# touch.net
KiCad netlist of a schematic drawn in EAGLE
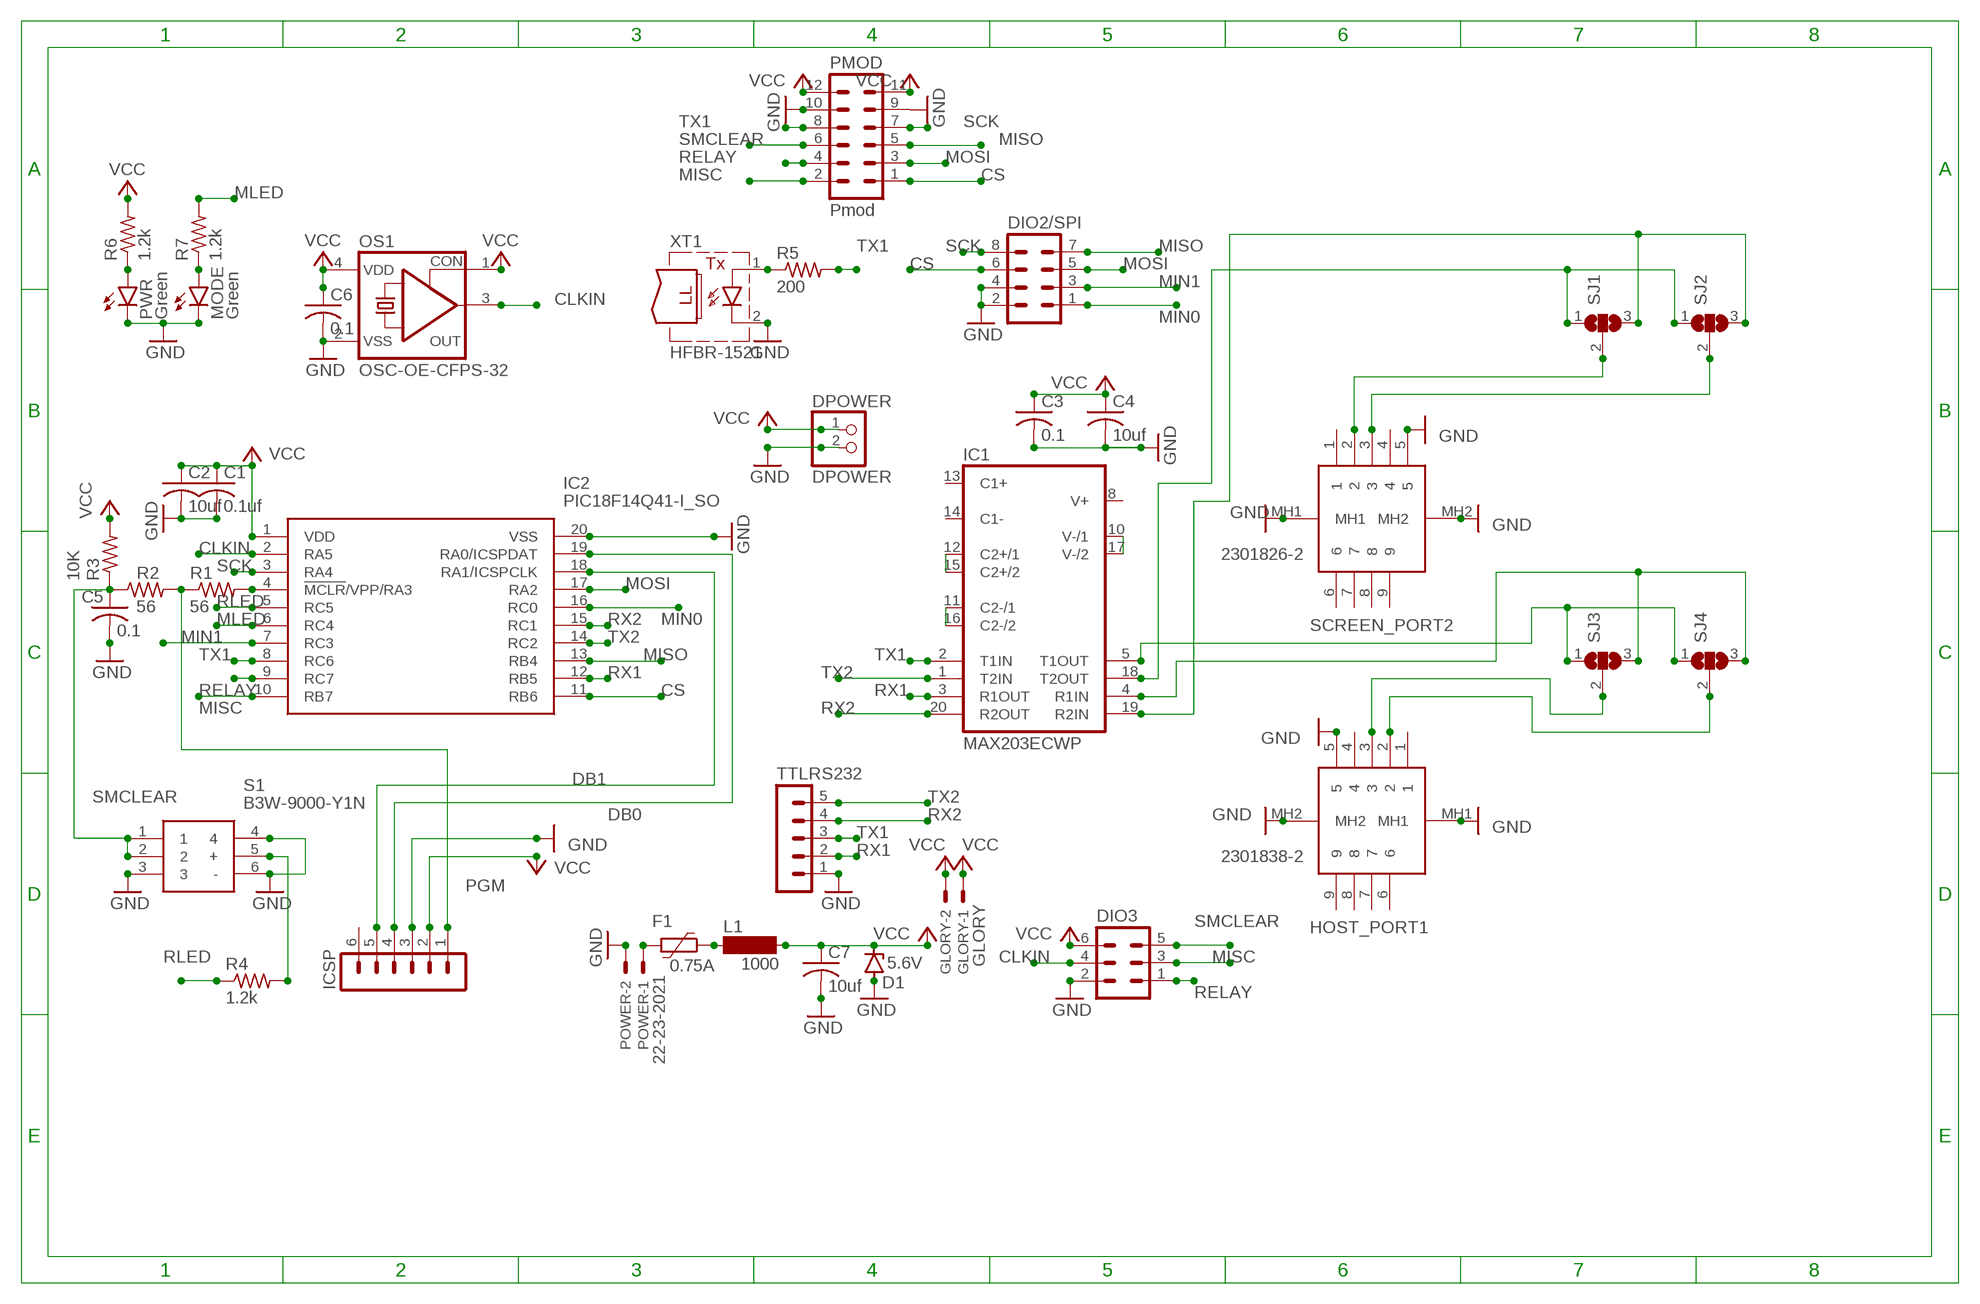
[diagram p0: schematic, sheet 1]

(export (version "E")
  (design (tool "Eeschema 10.0.6"))
  (components
    (comp (ref "C1")
      (value "0.1uf")
      (footprint "eagle-import:C0805")
      (libsource (lib "eagle-import") (part "C-USC0805"))
    )
    (comp (ref "C2")
      (value "10uf")
      (footprint "eagle-import:C0805")
      (libsource (lib "eagle-import") (part "C-USC0805"))
    )
    (comp (ref "C3")
      (value "0.1")
      (footprint "eagle-import:C0805")
      (libsource (lib "eagle-import") (part "C-USC0805"))
    )
    (comp (ref "C4")
      (value "10uf")
      (footprint "eagle-import:C0805")
      (libsource (lib "eagle-import") (part "C-USC0805"))
    )
    (comp (ref "C5")
      (value "0.1")
      (footprint "eagle-import:C0805")
      (libsource (lib "eagle-import") (part "C-USC0805"))
    )
    (comp (ref "C6")
      (value "0.1")
      (footprint "eagle-import:C0805")
      (libsource (lib "eagle-import") (part "C-USC0805"))
    )
    (comp (ref "C7")
      (value "10uf")
      (footprint "eagle-import:C0805")
      (libsource (lib "eagle-import") (part "C-USC0805"))
    )
    (comp (ref "D1")
      (value "5.6V")
      (footprint "eagle-import:SMB")
      (libsource (lib "eagle-import") (part "ZENER-DIODESMB"))
    )
    (comp (ref "DIO2/SPI")
      (value "MA04-2")
      (footprint "eagle-import:MA04-2")
      (libsource (lib "eagle-import") (part "MA04-2"))
    )
    (comp (ref "DIO3")
      (value "MA03-2")
      (footprint "eagle-import:MA03-2")
      (libsource (lib "eagle-import") (part "MA03-2"))
    )
    (comp (ref "DPOWER")
      (value "DPOWER")
      (footprint "eagle-import:1X02")
      (libsource (lib "eagle-import") (part "PINHD-1X2"))
    )
    (comp (ref "F1")
      (value "0.75A")
      (footprint "eagle-import:1206L")
      (fields (field (name "MF") "Littelfuse") (field (name "MPN") "1206L075SL"))
      (libsource (lib "eagle-import") (part "?1206L075SL"))
    )
    (comp (ref "GLORY")
      (value "GLORY")
      (footprint "eagle-import:22-23-2021")
      (fields (field (name "MF") "MOLEX") (field (name "MPN") "22-23-2021"))
      (libsource (lib "eagle-import") (part "22-23-2021"))
    )
    (comp (ref "HOST_PORT1")
      (value "2301838-2")
      (footprint "eagle-import:23018382")
      (fields (field (name "MOUSER_PART_NUMBER") "571-2301838-2"))
      (libsource (lib "eagle-import") (part "2301838-2"))
    )
    (comp (ref "IC1")
      (value "MAX203ECWP")
      (footprint "eagle-import:SO20L")
      (fields (field (name "MPN") "MAX203ECWP+G36"))
      (libsource (lib "eagle-import") (part "MAX203ECWP"))
    )
    (comp (ref "IC2")
      (value "PIC18F14Q41-I_SO")
      (footprint "eagle-import:SOIC127P1030X265-20N")
      (fields
        (field (name "MANUFACTURER_PART_NUMBER") "PIC18F14Q41-I/SO")
        (field (name "MOUSER_PART_NUMBER") "579-PIC18F14Q41-I/SO")
      )
      (libsource (lib "eagle-import") (part "PIC18F14Q41-I_SO"))
    )
    (comp (ref "ICSP")
      (value "MA06-1")
      (footprint "eagle-import:MA06-1")
      (libsource (lib "eagle-import") (part "MA06-1"))
    )
    (comp (ref "L1")
      (value "1000")
      (footprint "eagle-import:SM-1206")
      (libsource (lib "eagle-import") (part "SM-1206"))
    )
    (comp (ref "MODE")
      (value "Green")
      (footprint "eagle-import:CHIPLED_1206")
      (libsource (lib "eagle-import") (part "LEDCHIPLED_1206"))
    )
    (comp (ref "OS1")
      (value "OSC-OE-CFPS-32")
      (footprint "eagle-import:7.2X5.2-4-PAD")
      (libsource (lib "eagle-import") (part "OSC-OE-CFPS-32"))
    )
    (comp (ref "PMOD")
      (value "Pmod")
      (footprint "eagle-import:MA06-2")
      (libsource (lib "eagle-import") (part "MA06-2"))
    )
    (comp (ref "POWER")
      (value "22-23-2021")
      (footprint "eagle-import:22-23-2021")
      (fields (field (name "MF") "MOLEX"))
      (libsource (lib "eagle-import") (part "22-23-2021"))
    )
    (comp (ref "PWR")
      (value "Green")
      (footprint "eagle-import:CHIPLED_1206")
      (libsource (lib "eagle-import") (part "LEDCHIPLED_1206"))
    )
    (comp (ref "R1")
      (value "56")
      (footprint "eagle-import:R0805")
      (libsource (lib "eagle-import") (part "R-US_R0805"))
    )
    (comp (ref "R2")
      (value "56")
      (footprint "eagle-import:R0805")
      (libsource (lib "eagle-import") (part "R-US_R0805"))
    )
    (comp (ref "R3")
      (value "10K")
      (footprint "eagle-import:R0805")
      (libsource (lib "eagle-import") (part "R-US_R0805"))
    )
    (comp (ref "R4")
      (value "1.2k")
      (footprint "eagle-import:R0805")
      (libsource (lib "eagle-import") (part "R-US_R0805"))
    )
    (comp (ref "R5")
      (value "200")
      (footprint "eagle-import:R0805")
      (libsource (lib "eagle-import") (part "R-US_R0805"))
    )
    (comp (ref "R6")
      (value "1.2k")
      (footprint "eagle-import:R0805")
      (libsource (lib "eagle-import") (part "R-US_R0805"))
    )
    (comp (ref "R7")
      (value "1.2k")
      (footprint "eagle-import:R0805")
      (libsource (lib "eagle-import") (part "R-US_R0805"))
    )
    (comp (ref "S1")
      (value "B3W-9000-Y1N")
      (footprint "eagle-import:B3W-9_1-LED")
      (fields
        (field (name "MOUSER_PART_NUMBER") "653-B3W-9000-Y1N")
        (field (name "RS_PART_NUMBER") "0492777P")
      )
      (libsource (lib "eagle-import") (part "B3W-9000-Y1N"))
    )
    (comp (ref "SCREEN_PORT2")
      (value "2301826-2")
      (footprint "eagle-import:23018262")
      (fields (field (name "MOUSER_PART_NUMBER") "571-2301826-2"))
      (libsource (lib "eagle-import") (part "2301826-2"))
    )
    (comp (ref "SJ1")
      (value "SJ2W")
      (footprint "eagle-import:SJ_2")
      (libsource (lib "eagle-import") (part "SJ2W"))
    )
    (comp (ref "SJ2")
      (value "SJ2W")
      (footprint "eagle-import:SJ_2")
      (libsource (lib "eagle-import") (part "SJ2W"))
    )
    (comp (ref "SJ3")
      (value "SJ2W")
      (footprint "eagle-import:SJ_2")
      (libsource (lib "eagle-import") (part "SJ2W"))
    )
    (comp (ref "SJ4")
      (value "SJ2W")
      (footprint "eagle-import:SJ_2")
      (libsource (lib "eagle-import") (part "SJ2W"))
    )
    (comp (ref "TTLRS232")
      (value "MA05-1")
      (footprint "eagle-import:MA05-1")
      (libsource (lib "eagle-import") (part "MA05-1"))
    )
    (comp (ref "XT1")
      (value "HFBR-1521")
      (footprint "eagle-import:HFBR-15X3")
      (fields (field (name "MF") "AGILENT TECHNOLOGIES"))
      (libsource (lib "eagle-import") (part "HFBR-1521"))
    )
  )
  (nets
    (net (code "1") (name "/CLKIN") (class "Default")
      (node (ref "DIO3") (pin "4") (pinfunction "4_4") (pintype "passive"))
      (node (ref "IC2") (pin "2") (pinfunction "RA5_2") (pintype "bidirectional"))
      (node (ref "OS1") (pin "3") (pinfunction "OUT_3") (pintype "output"))
    )
    (net (code "2") (name "/CS") (class "Default")
      (node (ref "DIO2/SPI") (pin "6") (pinfunction "6_6") (pintype "passive"))
      (node (ref "IC2") (pin "11") (pinfunction "RB6_11") (pintype "bidirectional"))
      (node (ref "PMOD") (pin "1") (pinfunction "1_1") (pintype "passive"))
    )
    (net (code "3") (name "/DB0") (class "Default")
      (node (ref "IC2") (pin "19") (pinfunction "RA0/ICSPDAT_19") (pintype "bidirectional"))
      (node (ref "ICSP") (pin "4") (pinfunction "4_4") (pintype "passive"))
    )
    (net (code "4") (name "/DB1") (class "Default")
      (node (ref "IC2") (pin "18") (pinfunction "RA1/ICSPCLK_18") (pintype "bidirectional"))
      (node (ref "ICSP") (pin "5") (pinfunction "5_5") (pintype "passive"))
    )
    (net (code "5") (name "/MIN0") (class "Default")
      (node (ref "DIO2/SPI") (pin "1") (pinfunction "1_1") (pintype "passive"))
      (node (ref "IC2") (pin "16") (pinfunction "RC0_16") (pintype "bidirectional"))
    )
    (net (code "6") (name "/MIN1") (class "Default")
      (node (ref "DIO2/SPI") (pin "3") (pinfunction "3_3") (pintype "passive"))
      (node (ref "IC2") (pin "7") (pinfunction "RC3_7") (pintype "bidirectional"))
    )
    (net (code "7") (name "/MISC") (class "Default")
      (node (ref "DIO3") (pin "3") (pinfunction "3_3") (pintype "passive"))
      (node (ref "IC2") (pin "10") (pinfunction "RB7_10") (pintype "bidirectional"))
      (node (ref "PMOD") (pin "2") (pinfunction "2_2") (pintype "passive"))
    )
    (net (code "8") (name "/MISO") (class "Default")
      (node (ref "DIO2/SPI") (pin "7") (pinfunction "7_7") (pintype "passive"))
      (node (ref "IC2") (pin "13") (pinfunction "RB4_13") (pintype "bidirectional"))
      (node (ref "PMOD") (pin "5") (pinfunction "5_5") (pintype "passive"))
    )
    (net (code "9") (name "/MLED") (class "Default")
      (node (ref "IC2") (pin "6") (pinfunction "RC4_6") (pintype "bidirectional"))
      (node (ref "R7") (pin "2") (pinfunction "2_2") (pintype "passive"))
    )
    (net (code "10") (name "/MOSI") (class "Default")
      (node (ref "DIO2/SPI") (pin "5") (pinfunction "5_5") (pintype "passive"))
      (node (ref "IC2") (pin "17") (pinfunction "RA2_17") (pintype "bidirectional"))
      (node (ref "PMOD") (pin "3") (pinfunction "3_3") (pintype "passive"))
    )
    (net (code "11") (name "/PGM") (class "Default")
      (node (ref "ICSP") (pin "1") (pinfunction "1_1") (pintype "passive"))
      (node (ref "R1") (pin "1") (pinfunction "1_1") (pintype "passive"))
      (node (ref "R2") (pin "2") (pinfunction "2_2") (pintype "passive"))
    )
    (net (code "12") (name "/RELAY") (class "Default")
      (node (ref "DIO3") (pin "1") (pinfunction "1_1") (pintype "passive"))
      (node (ref "IC2") (pin "9") (pinfunction "RC7_9") (pintype "bidirectional"))
      (node (ref "PMOD") (pin "4") (pinfunction "4_4") (pintype "passive"))
    )
    (net (code "13") (name "/RLED") (class "Default")
      (node (ref "IC2") (pin "5") (pinfunction "RC5_5") (pintype "bidirectional"))
      (node (ref "R4") (pin "1") (pinfunction "1_1") (pintype "passive"))
    )
    (net (code "14") (name "/RX1") (class "Default")
      (node (ref "IC1") (pin "3") (pinfunction "R1OUT_3") (pintype "output"))
      (node (ref "IC2") (pin "12") (pinfunction "RB5_12") (pintype "bidirectional"))
      (node (ref "TTLRS232") (pin "2") (pinfunction "2_2") (pintype "passive"))
    )
    (net (code "15") (name "/RX2") (class "Default")
      (node (ref "IC1") (pin "20") (pinfunction "R2OUT_20") (pintype "output"))
      (node (ref "IC2") (pin "15") (pinfunction "RC1_15") (pintype "bidirectional"))
      (node (ref "TTLRS232") (pin "4") (pinfunction "4_4") (pintype "passive"))
    )
    (net (code "16") (name "/SCK") (class "Default")
      (node (ref "DIO2/SPI") (pin "8") (pinfunction "8_8") (pintype "passive"))
      (node (ref "IC2") (pin "3") (pinfunction "RA4_3") (pintype "bidirectional"))
      (node (ref "PMOD") (pin "7") (pinfunction "7_7") (pintype "passive"))
    )
    (net (code "17") (name "/SMCLEAR") (class "Default")
      (node (ref "C5") (pin "1") (pinfunction "1_1") (pintype "passive"))
      (node (ref "DIO3") (pin "5") (pinfunction "5_5") (pintype "passive"))
      (node (ref "PMOD") (pin "6") (pinfunction "6_6") (pintype "passive"))
      (node (ref "R2") (pin "1") (pinfunction "1_1") (pintype "passive"))
      (node (ref "R3") (pin "1") (pinfunction "1_1") (pintype "passive"))
      (node (ref "S1") (pin "1") (pinfunction "1_1") (pintype "bidirectional"))
      (node (ref "S1") (pin "2") (pinfunction "2_2") (pintype "bidirectional"))
    )
    (net (code "18") (name "/TX1") (class "Default")
      (node (ref "IC1") (pin "2") (pinfunction "T1IN_2") (pintype "input"))
      (node (ref "IC2") (pin "8") (pinfunction "RC6_8") (pintype "bidirectional"))
      (node (ref "PMOD") (pin "8") (pinfunction "8_8") (pintype "passive"))
      (node (ref "R5") (pin "2") (pinfunction "2_2") (pintype "passive"))
      (node (ref "TTLRS232") (pin "3") (pinfunction "3_3") (pintype "passive"))
    )
    (net (code "19") (name "/TX2") (class "Default")
      (node (ref "IC1") (pin "1") (pinfunction "T2IN_1") (pintype "input"))
      (node (ref "IC2") (pin "14") (pinfunction "RC2_14") (pintype "bidirectional"))
      (node (ref "TTLRS232") (pin "5") (pinfunction "5_5") (pintype "passive"))
    )
    (net (code "20") (name "GND") (class "Default")
      (node (ref "C1") (pin "2") (pinfunction "2_2") (pintype "passive"))
      (node (ref "C2") (pin "2") (pinfunction "2_2") (pintype "passive"))
      (node (ref "C3") (pin "2") (pinfunction "2_2") (pintype "passive"))
      (node (ref "C4") (pin "2") (pinfunction "2_2") (pintype "passive"))
      (node (ref "C5") (pin "2") (pinfunction "2_2") (pintype "passive"))
      (node (ref "C6") (pin "2") (pinfunction "2_2") (pintype "passive"))
      (node (ref "C7") (pin "2") (pinfunction "2_2") (pintype "passive"))
      (node (ref "D1") (pin "A") (pinfunction "A_A") (pintype "passive"))
      (node (ref "DIO2/SPI") (pin "2") (pinfunction "2_2") (pintype "passive"))
      (node (ref "DIO2/SPI") (pin "4") (pinfunction "4_4") (pintype "passive"))
      (node (ref "DIO3") (pin "2") (pinfunction "2_2") (pintype "passive"))
      (node (ref "DPOWER") (pin "2") (pinfunction "2_2") (pintype "passive"))
      (node (ref "HOST_PORT1") (pin "5") (pinfunction "5_5") (pintype "bidirectional"))
      (node (ref "HOST_PORT1") (pin "MH1") (pinfunction "MH1_MH1") (pintype "bidirectional"))
      (node (ref "HOST_PORT1") (pin "MH2") (pinfunction "MH2_MH2") (pintype "bidirectional"))
      (node (ref "IC2") (pin "20") (pinfunction "VSS_20") (pintype "bidirectional"))
      (node (ref "ICSP") (pin "3") (pinfunction "3_3") (pintype "passive"))
      (node (ref "MODE") (pin "C") (pinfunction "C_C") (pintype "passive"))
      (node (ref "OS1") (pin "2") (pinfunction "VSS_2") (pintype "power_in"))
      (node (ref "PMOD") (pin "10") (pinfunction "10_10") (pintype "passive"))
      (node (ref "PMOD") (pin "9") (pinfunction "9_9") (pintype "passive"))
      (node (ref "POWER") (pin "2") (pinfunction "S_2") (pintype "passive"))
      (node (ref "PWR") (pin "C") (pinfunction "C_C") (pintype "passive"))
      (node (ref "S1") (pin "3") (pinfunction "3_3") (pintype "bidirectional"))
      (node (ref "S1") (pin "4") (pinfunction "4_4") (pintype "bidirectional"))
      (node (ref "S1") (pin "6") (pinfunction "-_6") (pintype "bidirectional"))
      (node (ref "SCREEN_PORT2") (pin "5") (pinfunction "5_5") (pintype "bidirectional"))
      (node (ref "SCREEN_PORT2") (pin "MH1") (pinfunction "MH1_MH1") (pintype "bidirectional"))
      (node (ref "SCREEN_PORT2") (pin "MH2") (pinfunction "MH2_MH2") (pintype "bidirectional"))
      (node (ref "TTLRS232") (pin "1") (pinfunction "1_1") (pintype "passive"))
      (node (ref "XT1") (pin "2") (pinfunction "C_2") (pintype "passive"))
    )
    (net (code "21") (name "Net-(F1-Pad1)") (class "Default")
      (node (ref "F1") (pin "1") (pinfunction "1_1") (pintype "passive"))
      (node (ref "L1") (pin "1") (pinfunction "1_1") (pintype "passive"))
    )
    (net (code "22") (name "Net-(HOST_PORT1-Pad2)") (class "Default")
      (node (ref "HOST_PORT1") (pin "2") (pinfunction "2_2") (pintype "bidirectional"))
      (node (ref "SJ4") (pin "2") (pinfunction "2_2") (pintype "passive"))
    )
    (net (code "23") (name "Net-(HOST_PORT1-Pad3)") (class "Default")
      (node (ref "HOST_PORT1") (pin "3") (pinfunction "3_3") (pintype "bidirectional"))
      (node (ref "SJ3") (pin "2") (pinfunction "2_2") (pintype "passive"))
    )
    (net (code "24") (name "Net-(IC1A-C2+{slash}1)") (class "Default")
      (node (ref "IC1") (pin "12") (pinfunction "C2+/1_12") (pintype "passive"))
      (node (ref "IC1") (pin "15") (pinfunction "C2+/2_15") (pintype "passive"))
    )
    (net (code "25") (name "Net-(IC1A-C2-{slash}1)") (class "Default")
      (node (ref "IC1") (pin "11") (pinfunction "C2-/1_11") (pintype "passive"))
      (node (ref "IC1") (pin "16") (pinfunction "C2-/2_16") (pintype "passive"))
    )
    (net (code "26") (name "Net-(IC1A-R1IN)") (class "Default")
      (node (ref "IC1") (pin "4") (pinfunction "R1IN_4") (pintype "input"))
      (node (ref "SJ3") (pin "3") (pinfunction "3_3") (pintype "passive"))
      (node (ref "SJ4") (pin "3") (pinfunction "3_3") (pintype "passive"))
    )
    (net (code "27") (name "Net-(IC1A-R2IN)") (class "Default")
      (node (ref "IC1") (pin "19") (pinfunction "R2IN_19") (pintype "input"))
      (node (ref "SJ1") (pin "3") (pinfunction "3_3") (pintype "passive"))
      (node (ref "SJ2") (pin "3") (pinfunction "3_3") (pintype "passive"))
    )
    (net (code "28") (name "Net-(IC1A-T1OUT)") (class "Default")
      (node (ref "IC1") (pin "5") (pinfunction "T1OUT_5") (pintype "output"))
      (node (ref "SJ3") (pin "1") (pinfunction "1_1") (pintype "passive"))
      (node (ref "SJ4") (pin "1") (pinfunction "1_1") (pintype "passive"))
    )
    (net (code "29") (name "Net-(IC1A-T2OUT)") (class "Default")
      (node (ref "IC1") (pin "18") (pinfunction "T2OUT_18") (pintype "output"))
      (node (ref "SJ1") (pin "1") (pinfunction "1_1") (pintype "passive"))
      (node (ref "SJ2") (pin "1") (pinfunction "1_1") (pintype "passive"))
    )
    (net (code "30") (name "Net-(IC1A-V-{slash}1)") (class "Default")
      (node (ref "IC1") (pin "10") (pinfunction "V-/1_10") (pintype "passive"))
      (node (ref "IC1") (pin "17") (pinfunction "V-/2_17") (pintype "passive"))
    )
    (net (code "31") (name "Net-(IC2-~{MCLR}{slash}VPP{slash}RA3)") (class "Default")
      (node (ref "IC2") (pin "4") (pinfunction "~{MCLR}/VPP/RA3_4") (pintype "bidirectional"))
      (node (ref "R1") (pin "2") (pinfunction "2_2") (pintype "passive"))
    )
    (net (code "32") (name "Net-(MODE-PadA)") (class "Default")
      (node (ref "MODE") (pin "A") (pinfunction "A_A") (pintype "passive"))
      (node (ref "R7") (pin "1") (pinfunction "1_1") (pintype "passive"))
    )
    (net (code "33") (name "Net-(POWERA-S)") (class "Default")
      (node (ref "F1") (pin "2") (pinfunction "2_2") (pintype "passive"))
      (node (ref "POWER") (pin "1") (pinfunction "S_1") (pintype "passive"))
    )
    (net (code "34") (name "Net-(PWR-PadA)") (class "Default")
      (node (ref "PWR") (pin "A") (pinfunction "A_A") (pintype "passive"))
      (node (ref "R6") (pin "1") (pinfunction "1_1") (pintype "passive"))
    )
    (net (code "35") (name "Net-(S1-+)") (class "Default")
      (node (ref "R4") (pin "2") (pinfunction "2_2") (pintype "passive"))
      (node (ref "S1") (pin "5") (pinfunction "+_5") (pintype "bidirectional"))
    )
    (net (code "36") (name "Net-(SCREEN_PORT2-Pad2)") (class "Default")
      (node (ref "SCREEN_PORT2") (pin "2") (pinfunction "2_2") (pintype "bidirectional"))
      (node (ref "SJ1") (pin "2") (pinfunction "2_2") (pintype "passive"))
    )
    (net (code "37") (name "Net-(SCREEN_PORT2-Pad3)") (class "Default")
      (node (ref "SCREEN_PORT2") (pin "3") (pinfunction "3_3") (pintype "bidirectional"))
      (node (ref "SJ2") (pin "2") (pinfunction "2_2") (pintype "passive"))
    )
    (net (code "38") (name "Net-(XT1-A)") (class "Default")
      (node (ref "R5") (pin "1") (pinfunction "1_1") (pintype "passive"))
      (node (ref "XT1") (pin "1") (pinfunction "A_1") (pintype "passive"))
    )
    (net (code "39") (name "VCC") (class "Default")
      (node (ref "C1") (pin "1") (pinfunction "1_1") (pintype "passive"))
      (node (ref "C2") (pin "1") (pinfunction "1_1") (pintype "passive"))
      (node (ref "C3") (pin "1") (pinfunction "1_1") (pintype "passive"))
      (node (ref "C4") (pin "1") (pinfunction "1_1") (pintype "passive"))
      (node (ref "C6") (pin "1") (pinfunction "1_1") (pintype "passive"))
      (node (ref "C7") (pin "1") (pinfunction "1_1") (pintype "passive"))
      (node (ref "D1") (pin "C") (pinfunction "C_C") (pintype "passive"))
      (node (ref "DIO3") (pin "6") (pinfunction "6_6") (pintype "passive"))
      (node (ref "DPOWER") (pin "1") (pinfunction "1_1") (pintype "passive"))
      (node (ref "GLORY") (pin "1") (pinfunction "S_1") (pintype "passive"))
      (node (ref "GLORY") (pin "2") (pinfunction "S_2") (pintype "passive"))
      (node (ref "IC2") (pin "1") (pinfunction "VDD_1") (pintype "bidirectional"))
      (node (ref "ICSP") (pin "2") (pinfunction "2_2") (pintype "passive"))
      (node (ref "L1") (pin "2") (pinfunction "2_2") (pintype "passive"))
      (node (ref "OS1") (pin "1") (pinfunction "CON_1") (pintype "input"))
      (node (ref "OS1") (pin "4") (pinfunction "VDD_4") (pintype "power_in"))
      (node (ref "PMOD") (pin "11") (pinfunction "11_11") (pintype "passive"))
      (node (ref "PMOD") (pin "12") (pinfunction "12_12") (pintype "passive"))
      (node (ref "R3") (pin "2") (pinfunction "2_2") (pintype "passive"))
      (node (ref "R6") (pin "2") (pinfunction "2_2") (pintype "passive"))
    )
    (net (code "40") (name "unconnected-(HOST_PORT1-Pad1)") (class "Default")
      (node (ref "HOST_PORT1") (pin "1") (pinfunction "1_1") (pintype "bidirectional"))
    )
    (net (code "41") (name "unconnected-(HOST_PORT1-Pad4)") (class "Default")
      (node (ref "HOST_PORT1") (pin "4") (pinfunction "4_4") (pintype "bidirectional"))
    )
    (net (code "42") (name "unconnected-(HOST_PORT1-Pad6)") (class "Default")
      (node (ref "HOST_PORT1") (pin "6") (pinfunction "6_6") (pintype "bidirectional"))
    )
    (net (code "43") (name "unconnected-(HOST_PORT1-Pad7)") (class "Default")
      (node (ref "HOST_PORT1") (pin "7") (pinfunction "7_7") (pintype "bidirectional"))
    )
    (net (code "44") (name "unconnected-(HOST_PORT1-Pad8)") (class "Default")
      (node (ref "HOST_PORT1") (pin "8") (pinfunction "8_8") (pintype "bidirectional"))
    )
    (net (code "45") (name "unconnected-(HOST_PORT1-Pad9)") (class "Default")
      (node (ref "HOST_PORT1") (pin "9") (pinfunction "9_9") (pintype "bidirectional"))
    )
    (net (code "46") (name "unconnected-(IC1A-C1+-Pad13)") (class "Default")
      (node (ref "IC1") (pin "13") (pinfunction "C1+_13") (pintype "passive"))
    )
    (net (code "47") (name "unconnected-(IC1A-C1--Pad14)") (class "Default")
      (node (ref "IC1") (pin "14") (pinfunction "C1-_14") (pintype "passive"))
    )
    (net (code "48") (name "unconnected-(IC1A-V+-Pad8)") (class "Default")
      (node (ref "IC1") (pin "8") (pinfunction "V+_8") (pintype "passive"))
    )
    (net (code "49") (name "unconnected-(ICSP-Pad6)") (class "Default")
      (node (ref "ICSP") (pin "6") (pinfunction "6_6") (pintype "passive"))
    )
    (net (code "50") (name "unconnected-(SCREEN_PORT2-Pad1)") (class "Default")
      (node (ref "SCREEN_PORT2") (pin "1") (pinfunction "1_1") (pintype "bidirectional"))
    )
    (net (code "51") (name "unconnected-(SCREEN_PORT2-Pad4)") (class "Default")
      (node (ref "SCREEN_PORT2") (pin "4") (pinfunction "4_4") (pintype "bidirectional"))
    )
    (net (code "52") (name "unconnected-(SCREEN_PORT2-Pad6)") (class "Default")
      (node (ref "SCREEN_PORT2") (pin "6") (pinfunction "6_6") (pintype "bidirectional"))
    )
    (net (code "53") (name "unconnected-(SCREEN_PORT2-Pad7)") (class "Default")
      (node (ref "SCREEN_PORT2") (pin "7") (pinfunction "7_7") (pintype "bidirectional"))
    )
    (net (code "54") (name "unconnected-(SCREEN_PORT2-Pad8)") (class "Default")
      (node (ref "SCREEN_PORT2") (pin "8") (pinfunction "8_8") (pintype "bidirectional"))
    )
    (net (code "55") (name "unconnected-(SCREEN_PORT2-Pad9)") (class "Default")
      (node (ref "SCREEN_PORT2") (pin "9") (pinfunction "9_9") (pintype "bidirectional"))
    )
  )
)
